# LiPo-PSU.net
KiCad netlist of a schematic drawn in EAGLE
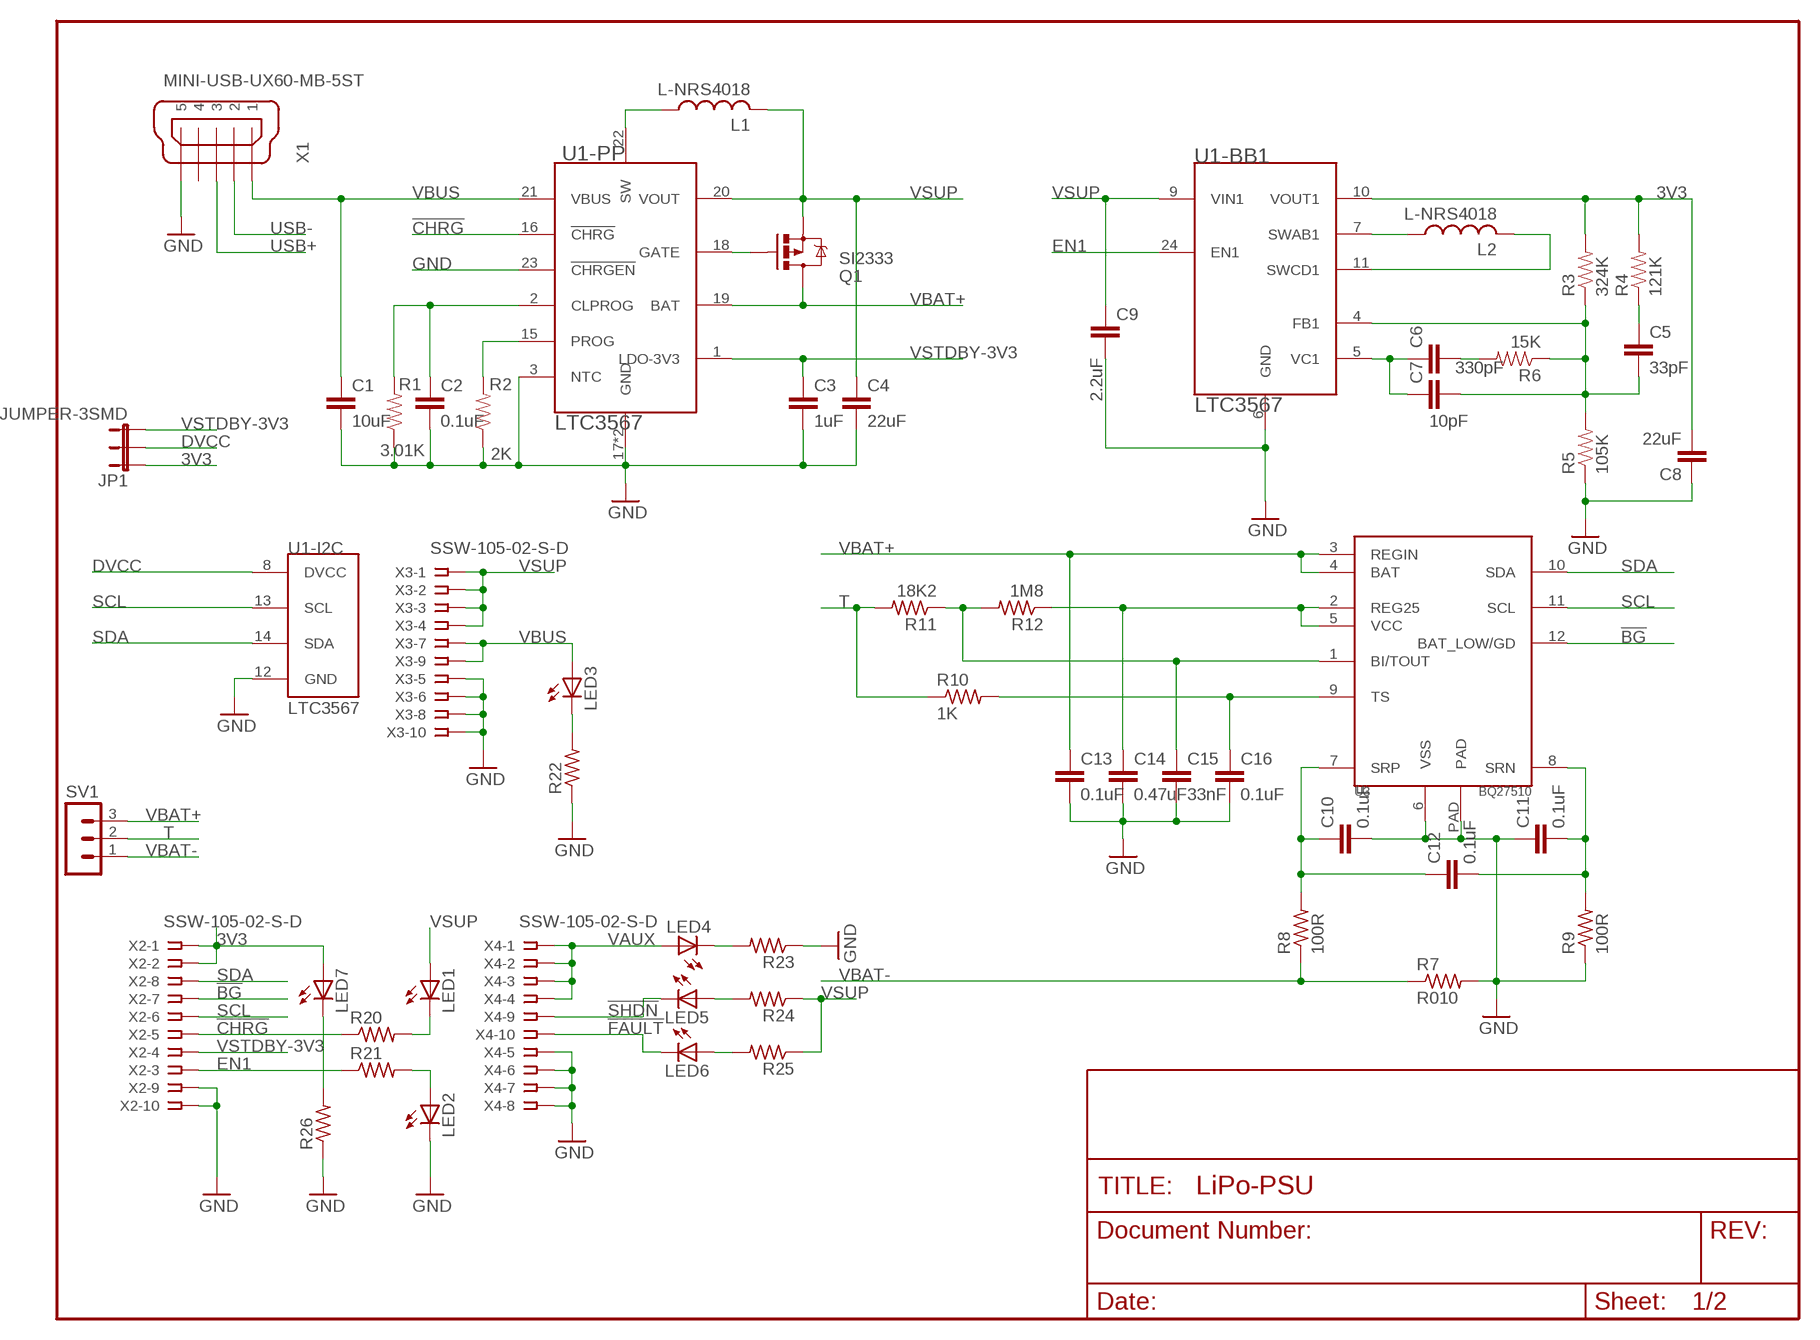
[diagram p0: schematic, sheet 1]
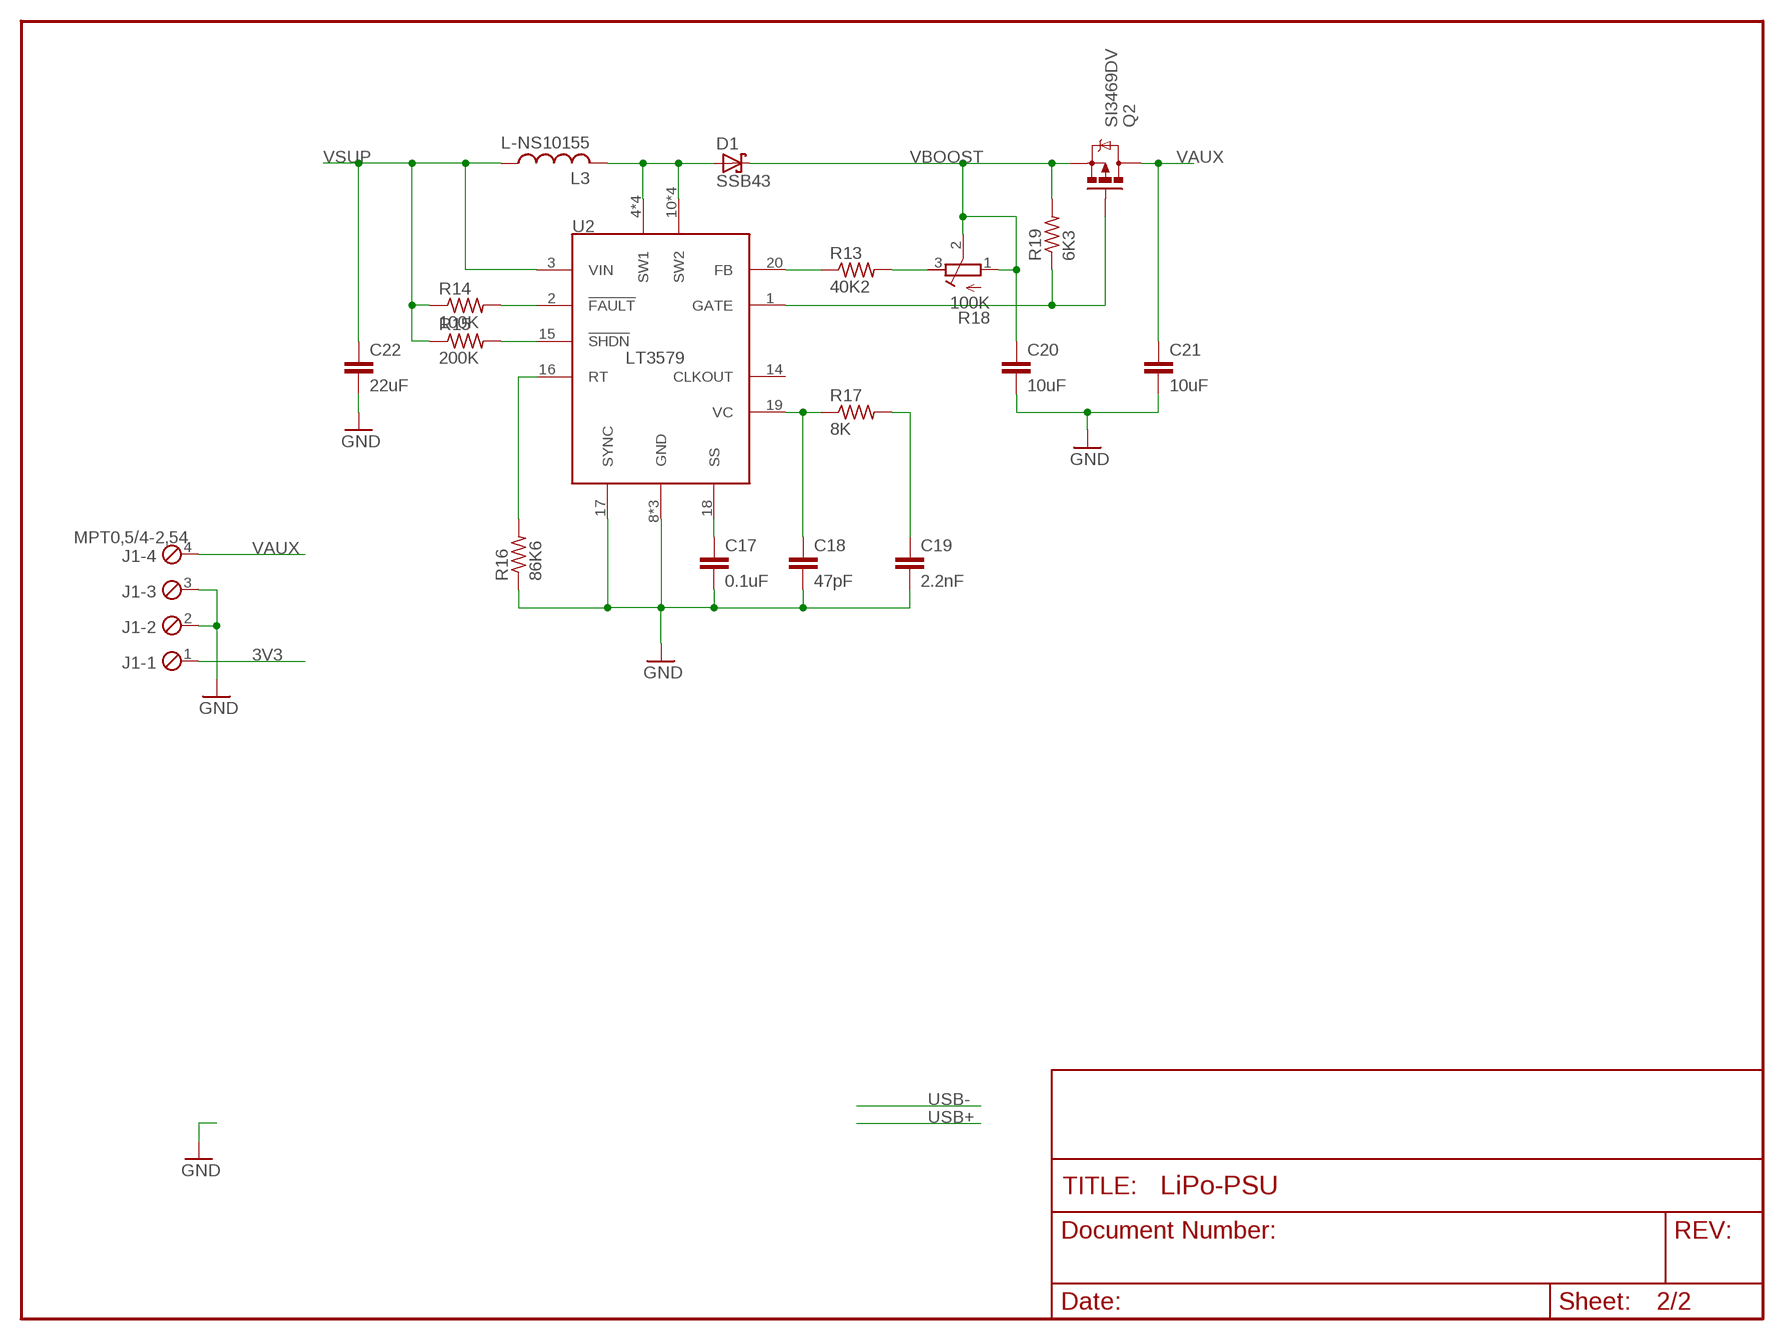
[diagram p1: schematic, sheet 2]

(export (version "E")
  (design (tool "Eeschema 10.0.6"))
  (components
    (comp (ref "C17")
      (value "0.1uF")
      (footprint "eagle-import:C0402")
      (libsource (lib "eagle-import") (part "C-EUC0402"))
    )
    (comp (ref "C18")
      (value "47pF")
      (footprint "eagle-import:C0402")
      (libsource (lib "eagle-import") (part "C-EUC0402"))
    )
    (comp (ref "C19")
      (value "2.2nF")
      (footprint "eagle-import:C0402")
      (libsource (lib "eagle-import") (part "C-EUC0402"))
    )
    (comp (ref "C20")
      (value "10uF")
      (footprint "eagle-import:C0805")
      (libsource (lib "eagle-import") (part "C-EUC0805"))
    )
    (comp (ref "C21")
      (value "10uF")
      (footprint "eagle-import:C0805")
      (libsource (lib "eagle-import") (part "C-EUC0805"))
    )
    (comp (ref "C22")
      (value "22uF")
      (footprint "eagle-import:C0805")
      (libsource (lib "eagle-import") (part "C-EUC0805"))
    )
    (comp (ref "D1")
      (value "SSB43")
      (footprint "eagle-import:SMB")
      (libsource (lib "eagle-import") (part "MBRS130LT3"))
    )
    (comp (ref "J1")
      (value "MPT0,5/4-2,54")
      (footprint "eagle-import:MPT0,5_4-2,54")
      (libsource (lib "eagle-import") (part "MPT0,5/4-2,54"))
    )
    (comp (ref "L3")
      (value "L-NS10155")
      (footprint "eagle-import:NS10155")
      (libsource (lib "eagle-import") (part "L-NS10155"))
    )
    (comp (ref "Q2")
      (value "SI3469DV")
      (footprint "eagle-import:TSOP-6")
      (libsource (lib "eagle-import") (part "MOSFET-PCHANNELTSOP6"))
    )
    (comp (ref "R13")
      (value "40K2")
      (footprint "eagle-import:R0402")
      (libsource (lib "eagle-import") (part "R-US_R0402"))
    )
    (comp (ref "R14")
      (value "100K")
      (footprint "eagle-import:R0402")
      (libsource (lib "eagle-import") (part "R-US_R0402"))
    )
    (comp (ref "R15")
      (value "200K")
      (footprint "eagle-import:R0402")
      (libsource (lib "eagle-import") (part "R-US_R0402"))
    )
    (comp (ref "R16")
      (value "86K6")
      (footprint "eagle-import:R0402")
      (libsource (lib "eagle-import") (part "R-US_R0402"))
    )
    (comp (ref "R17")
      (value "8K")
      (footprint "eagle-import:R0402")
      (libsource (lib "eagle-import") (part "R-US_R0402"))
    )
    (comp (ref "R18")
      (value "100K")
      (footprint "eagle-import:RTRIM3214W")
      (libsource (lib "eagle-import") (part "R-TRIMM3214W"))
    )
    (comp (ref "R19")
      (value "6K3")
      (footprint "eagle-import:R0402")
      (libsource (lib "eagle-import") (part "R-US_R0402"))
    )
    (comp (ref "U2")
      (value "LT3579")
      (footprint "eagle-import:QFN20-4X5(UFD)")
      (libsource (lib "eagle-import") (part "LT3579"))
    )
    (comp (ref "C1")
      (value "10uF")
      (footprint "eagle-import:0805")
      (libsource (lib "eagle-import") (part "CAP0805"))
    )
    (comp (ref "C2")
      (value "0.1uF")
      (footprint "eagle-import:0402-CAP")
      (libsource (lib "eagle-import") (part "CAP0402-CAP"))
    )
    (comp (ref "C3")
      (value "1uF")
      (footprint "eagle-import:0402-CAP")
      (libsource (lib "eagle-import") (part "CAP0402-CAP"))
    )
    (comp (ref "C4")
      (value "22uF")
      (footprint "eagle-import:0805")
      (libsource (lib "eagle-import") (part "CAP0805"))
    )
    (comp (ref "C5")
      (value "33pF")
      (footprint "eagle-import:0402-CAP")
      (libsource (lib "eagle-import") (part "CAP0402-CAP"))
    )
    (comp (ref "C6")
      (value "330pF")
      (footprint "eagle-import:0402-CAP")
      (libsource (lib "eagle-import") (part "CAP0402-CAP"))
    )
    (comp (ref "C7")
      (value "10pF")
      (footprint "eagle-import:0402-CAP")
      (libsource (lib "eagle-import") (part "CAP0402-CAP"))
    )
    (comp (ref "C8")
      (value "22uF")
      (footprint "eagle-import:0805")
      (libsource (lib "eagle-import") (part "CAP0805"))
    )
    (comp (ref "C9")
      (value "2.2uF")
      (footprint "eagle-import:0402-CAP")
      (libsource (lib "eagle-import") (part "CAP0402-CAP"))
    )
    (comp (ref "C10")
      (value "0.1uF")
      (footprint "eagle-import:C0402")
      (libsource (lib "eagle-import") (part "C-EUC0402"))
    )
    (comp (ref "C11")
      (value "0.1uF")
      (footprint "eagle-import:C0402")
      (libsource (lib "eagle-import") (part "C-EUC0402"))
    )
    (comp (ref "C12")
      (value "0.1uF")
      (footprint "eagle-import:C0402")
      (libsource (lib "eagle-import") (part "C-EUC0402"))
    )
    (comp (ref "C13")
      (value "0.1uF")
      (footprint "eagle-import:C0402")
      (libsource (lib "eagle-import") (part "C-EUC0402"))
    )
    (comp (ref "C14")
      (value "0.47uF")
      (footprint "eagle-import:C0402")
      (libsource (lib "eagle-import") (part "C-EUC0402"))
    )
    (comp (ref "C15")
      (value "33nF")
      (footprint "eagle-import:C0402")
      (libsource (lib "eagle-import") (part "C-EUC0402"))
    )
    (comp (ref "C16")
      (value "0.1uF")
      (footprint "eagle-import:C0402")
      (libsource (lib "eagle-import") (part "C-EUC0402"))
    )
    (comp (ref "JP1")
      (value "JUMPER-3SMD")
      (footprint "eagle-import:SJ_3")
      (libsource (lib "eagle-import") (part "JUMPER-3SMD"))
    )
    (comp (ref "L1")
      (value "L-NRS4018")
      (footprint "eagle-import:NR(S)401X")
      (libsource (lib "eagle-import") (part "L-NRS4018"))
    )
    (comp (ref "L2")
      (value "L-NRS4018")
      (footprint "eagle-import:NR(S)401X")
      (libsource (lib "eagle-import") (part "L-NRS4018"))
    )
    (comp (ref "LED1")
      (value "LEDCHIP-LED0603")
      (footprint "eagle-import:CHIP-LED0603")
      (libsource (lib "eagle-import") (part "LEDCHIP-LED0603"))
    )
    (comp (ref "LED2")
      (value "LEDCHIP-LED0603")
      (footprint "eagle-import:CHIP-LED0603")
      (libsource (lib "eagle-import") (part "LEDCHIP-LED0603"))
    )
    (comp (ref "LED3")
      (value "LEDCHIP-LED0603")
      (footprint "eagle-import:CHIP-LED0603")
      (libsource (lib "eagle-import") (part "LEDCHIP-LED0603"))
    )
    (comp (ref "LED4")
      (value "LEDCHIP-LED0603")
      (footprint "eagle-import:CHIP-LED0603")
      (libsource (lib "eagle-import") (part "LEDCHIP-LED0603"))
    )
    (comp (ref "LED5")
      (value "LEDCHIP-LED0603")
      (footprint "eagle-import:CHIP-LED0603")
      (libsource (lib "eagle-import") (part "LEDCHIP-LED0603"))
    )
    (comp (ref "LED6")
      (value "LEDCHIP-LED0603")
      (footprint "eagle-import:CHIP-LED0603")
      (libsource (lib "eagle-import") (part "LEDCHIP-LED0603"))
    )
    (comp (ref "LED7")
      (value "LEDCHIP-LED0603")
      (footprint "eagle-import:CHIP-LED0603")
      (libsource (lib "eagle-import") (part "LEDCHIP-LED0603"))
    )
    (comp (ref "Q1")
      (value "SI2333")
      (footprint "eagle-import:SOT23-3")
      (libsource (lib "eagle-import") (part "SI2333"))
    )
    (comp (ref "R1")
      (value "3.01K")
      (footprint "eagle-import:0402-RES")
      (libsource (lib "eagle-import") (part "RESISTOR0402-RES"))
    )
    (comp (ref "R2")
      (value "2K")
      (footprint "eagle-import:0402-RES")
      (libsource (lib "eagle-import") (part "RESISTOR0402-RES"))
    )
    (comp (ref "R3")
      (value "324K")
      (footprint "eagle-import:0402-RES")
      (libsource (lib "eagle-import") (part "RESISTOR0402-RES"))
    )
    (comp (ref "R4")
      (value "121K")
      (footprint "eagle-import:0402-RES")
      (libsource (lib "eagle-import") (part "RESISTOR0402-RES"))
    )
    (comp (ref "R5")
      (value "105K")
      (footprint "eagle-import:0402-RES")
      (libsource (lib "eagle-import") (part "RESISTOR0402-RES"))
    )
    (comp (ref "R6")
      (value "15K")
      (footprint "eagle-import:0402-RES")
      (libsource (lib "eagle-import") (part "RESISTOR0402-RES"))
    )
    (comp (ref "R7")
      (value "R010")
      (footprint "eagle-import:R2512")
      (libsource (lib "eagle-import") (part "R-US_R2512"))
    )
    (comp (ref "R8")
      (value "100R")
      (footprint "eagle-import:R0402")
      (libsource (lib "eagle-import") (part "R-US_R0402"))
    )
    (comp (ref "R9")
      (value "100R")
      (footprint "eagle-import:R0402")
      (libsource (lib "eagle-import") (part "R-US_R0402"))
    )
    (comp (ref "R10")
      (value "1K")
      (footprint "eagle-import:R0402")
      (libsource (lib "eagle-import") (part "R-US_R0402"))
    )
    (comp (ref "R11")
      (value "18K2")
      (footprint "eagle-import:R0402")
      (libsource (lib "eagle-import") (part "R-US_R0402"))
    )
    (comp (ref "R12")
      (value "1M8")
      (footprint "eagle-import:R0402")
      (libsource (lib "eagle-import") (part "R-US_R0402"))
    )
    (comp (ref "R20")
      (value "R-US_R0402")
      (footprint "eagle-import:R0402")
      (libsource (lib "eagle-import") (part "R-US_R0402"))
    )
    (comp (ref "R21")
      (value "R-US_R0402")
      (footprint "eagle-import:R0402")
      (libsource (lib "eagle-import") (part "R-US_R0402"))
    )
    (comp (ref "R22")
      (value "R-US_R0402")
      (footprint "eagle-import:R0402")
      (libsource (lib "eagle-import") (part "R-US_R0402"))
    )
    (comp (ref "R23")
      (value "R-US_R0402")
      (footprint "eagle-import:R0402")
      (libsource (lib "eagle-import") (part "R-US_R0402"))
    )
    (comp (ref "R24")
      (value "R-US_R0402")
      (footprint "eagle-import:R0402")
      (libsource (lib "eagle-import") (part "R-US_R0402"))
    )
    (comp (ref "R25")
      (value "R-US_R0402")
      (footprint "eagle-import:R0402")
      (libsource (lib "eagle-import") (part "R-US_R0402"))
    )
    (comp (ref "R26")
      (value "R-US_R0402")
      (footprint "eagle-import:R0402")
      (libsource (lib "eagle-import") (part "R-US_R0402"))
    )
    (comp (ref "SV1")
      (value "MA03-1")
      (footprint "eagle-import:MA03-1")
      (libsource (lib "eagle-import") (part "MA03-1"))
    )
    (comp (ref "U1")
      (value "LTC3567")
      (footprint "eagle-import:QFN24-4X4(UF)")
      (libsource (lib "eagle-import") (part "LTC3567"))
    )
    (comp (ref "U3")
      (value "BQ27510")
      (footprint "eagle-import:DRZ(S-PDSO-N12)")
      (libsource (lib "eagle-import") (part "BQ27510"))
    )
    (comp (ref "X1")
      (value "MINI-USB-UX60-MB-5ST")
      (footprint "eagle-import:UX60-MB-5ST")
      (libsource (lib "eagle-import") (part "MINI-USB-UX60-MB-5ST"))
    )
    (comp (ref "X2")
      (value "SSW-105-02-S-D")
      (footprint "eagle-import:SSW-105-02-S-D")
      (libsource (lib "eagle-import") (part "SSW-105-02-S-D"))
    )
    (comp (ref "X3")
      (value "SSW-105-02-S-D")
      (footprint "eagle-import:SSW-105-02-S-D")
      (libsource (lib "eagle-import") (part "SSW-105-02-S-D"))
    )
    (comp (ref "X4")
      (value "SSW-105-02-S-D")
      (footprint "eagle-import:SSW-105-02-S-D")
      (libsource (lib "eagle-import") (part "SSW-105-02-S-D"))
    )
  )
  (nets
    (net (code "1") (name "3V3") (class "Default")
      (node (ref "C8") (pin "2") (pinfunction "2_2") (pintype "passive"))
      (node (ref "J1") (pin "1") (pinfunction "1_1") (pintype "passive"))
      (node (ref "JP1") (pin "1") (pinfunction "1_1") (pintype "passive"))
      (node (ref "LED7") (pin "A") (pinfunction "A_A") (pintype "passive"))
      (node (ref "R3") (pin "2") (pinfunction "2_2") (pintype "passive"))
      (node (ref "R4") (pin "2") (pinfunction "2_2") (pintype "passive"))
      (node (ref "U1") (pin "10") (pinfunction "VOUT1_10") (pintype "output"))
      (node (ref "X2") (pin "1") (pinfunction "1_1") (pintype "passive"))
      (node (ref "X2") (pin "2") (pinfunction "1_2") (pintype "passive"))
    )
    (net (code "2") (name "DVCC") (class "Default")
      (node (ref "JP1") (pin "2") (pinfunction "2_2") (pintype "passive"))
      (node (ref "U1") (pin "8") (pinfunction "DVCC_8") (pintype "input"))
    )
    (net (code "3") (name "EN1") (class "Default")
      (node (ref "R21") (pin "1") (pinfunction "1_1") (pintype "passive"))
      (node (ref "U1") (pin "24") (pinfunction "EN1_24") (pintype "input"))
      (node (ref "X2") (pin "3") (pinfunction "1_3") (pintype "passive"))
    )
    (net (code "4") (name "GND") (class "Default")
      (node (ref "C1") (pin "2") (pinfunction "2_2") (pintype "passive"))
      (node (ref "C10") (pin "2") (pinfunction "2_2") (pintype "passive"))
      (node (ref "C11") (pin "1") (pinfunction "1_1") (pintype "passive"))
      (node (ref "C13") (pin "2") (pinfunction "2_2") (pintype "passive"))
      (node (ref "C14") (pin "2") (pinfunction "2_2") (pintype "passive"))
      (node (ref "C15") (pin "2") (pinfunction "2_2") (pintype "passive"))
      (node (ref "C16") (pin "2") (pinfunction "2_2") (pintype "passive"))
      (node (ref "C17") (pin "2") (pinfunction "2_2") (pintype "passive"))
      (node (ref "C18") (pin "2") (pinfunction "2_2") (pintype "passive"))
      (node (ref "C19") (pin "2") (pinfunction "2_2") (pintype "passive"))
      (node (ref "C2") (pin "2") (pinfunction "2_2") (pintype "passive"))
      (node (ref "C20") (pin "2") (pinfunction "2_2") (pintype "passive"))
      (node (ref "C21") (pin "2") (pinfunction "2_2") (pintype "passive"))
      (node (ref "C22") (pin "2") (pinfunction "2_2") (pintype "passive"))
      (node (ref "C3") (pin "2") (pinfunction "2_2") (pintype "passive"))
      (node (ref "C4") (pin "2") (pinfunction "2_2") (pintype "passive"))
      (node (ref "C8") (pin "1") (pinfunction "1_1") (pintype "passive"))
      (node (ref "C9") (pin "2") (pinfunction "2_2") (pintype "passive"))
      (node (ref "J1") (pin "2") (pinfunction "1_2") (pintype "passive"))
      (node (ref "J1") (pin "3") (pinfunction "1_3") (pintype "passive"))
      (node (ref "LED2") (pin "C") (pinfunction "C_C") (pintype "passive"))
      (node (ref "R1") (pin "1") (pinfunction "1_1") (pintype "passive"))
      (node (ref "R16") (pin "1") (pinfunction "1_1") (pintype "passive"))
      (node (ref "R2") (pin "1") (pinfunction "1_1") (pintype "passive"))
      (node (ref "R22") (pin "1") (pinfunction "1_1") (pintype "passive"))
      (node (ref "R23") (pin "1") (pinfunction "1_1") (pintype "passive"))
      (node (ref "R26") (pin "1") (pinfunction "1_1") (pintype "passive"))
      (node (ref "R5") (pin "1") (pinfunction "1_1") (pintype "passive"))
      (node (ref "R7") (pin "2") (pinfunction "2_2") (pintype "passive"))
      (node (ref "R9") (pin "1") (pinfunction "1_1") (pintype "passive"))
      (node (ref "U1") (pin "12") (pinfunction "GND_12") (pintype "power_in"))
      (node (ref "U1") (pin "17") (pinfunction "GND_17") (pintype "power_in"))
      (node (ref "U1") (pin "23") (pinfunction "~{CHRGEN}_23") (pintype "input"))
      (node (ref "U1") (pin "3") (pinfunction "NTC_3") (pintype "bidirectional"))
      (node (ref "U1") (pin "6") (pinfunction "GND_6") (pintype "power_in"))
      (node (ref "U1") (pin "PAD") (pinfunction "GND_PAD") (pintype "power_in"))
      (node (ref "U2") (pin "17") (pinfunction "SYNC_17") (pintype "input"))
      (node (ref "U2") (pin "8") (pinfunction "GND_8") (pintype "power_in"))
      (node (ref "U2") (pin "9") (pinfunction "GND_9") (pintype "power_in"))
      (node (ref "U2") (pin "PAD") (pinfunction "GND_PAD") (pintype "power_in"))
      (node (ref "U3") (pin "6") (pinfunction "VSS_6") (pintype "power_in"))
      (node (ref "U3") (pin "PAD") (pinfunction "PAD_PAD") (pintype "power_in"))
      (node (ref "X1") (pin "5") (pinfunction "5_5") (pintype "input"))
      (node (ref "X2") (pin "10") (pinfunction "1_10") (pintype "passive"))
      (node (ref "X2") (pin "9") (pinfunction "1_9") (pintype "passive"))
      (node (ref "X3") (pin "10") (pinfunction "1_10") (pintype "passive"))
      (node (ref "X3") (pin "5") (pinfunction "1_5") (pintype "passive"))
      (node (ref "X3") (pin "6") (pinfunction "1_6") (pintype "passive"))
      (node (ref "X3") (pin "8") (pinfunction "1_8") (pintype "passive"))
      (node (ref "X4") (pin "5") (pinfunction "1_5") (pintype "passive"))
      (node (ref "X4") (pin "6") (pinfunction "1_6") (pintype "passive"))
      (node (ref "X4") (pin "7") (pinfunction "1_7") (pintype "passive"))
      (node (ref "X4") (pin "8") (pinfunction "1_8") (pintype "passive"))
    )
    (net (code "5") (name "Net-(C5-Pad1)") (class "Default")
      (node (ref "C5") (pin "1") (pinfunction "1_1") (pintype "passive"))
      (node (ref "R4") (pin "1") (pinfunction "1_1") (pintype "passive"))
    )
    (net (code "6") (name "Net-(C6-Pad2)") (class "Default")
      (node (ref "C6") (pin "2") (pinfunction "2_2") (pintype "passive"))
      (node (ref "R6") (pin "2") (pinfunction "2_2") (pintype "passive"))
    )
    (net (code "7") (name "Net-(C19-Pad1)") (class "Default")
      (node (ref "C19") (pin "1") (pinfunction "1_1") (pintype "passive"))
      (node (ref "R17") (pin "2") (pinfunction "2_2") (pintype "passive"))
    )
    (net (code "8") (name "Net-(D1-PadA)") (class "Default")
      (node (ref "D1") (pin "A") (pinfunction "A_A") (pintype "passive"))
      (node (ref "L3") (pin "2") (pinfunction "2_2") (pintype "passive"))
      (node (ref "U2") (pin "10") (pinfunction "SW2_10") (pintype "bidirectional"))
      (node (ref "U2") (pin "11") (pinfunction "SW2_11") (pintype "bidirectional"))
      (node (ref "U2") (pin "12") (pinfunction "SW2_12") (pintype "bidirectional"))
      (node (ref "U2") (pin "13") (pinfunction "SW2_13") (pintype "bidirectional"))
      (node (ref "U2") (pin "4") (pinfunction "SW1_4") (pintype "bidirectional"))
      (node (ref "U2") (pin "5") (pinfunction "SW1_5") (pintype "bidirectional"))
      (node (ref "U2") (pin "6") (pinfunction "SW1_6") (pintype "bidirectional"))
      (node (ref "U2") (pin "7") (pinfunction "SW1_7") (pintype "bidirectional"))
    )
    (net (code "9") (name "Net-(LED1-PadC)") (class "Default")
      (node (ref "LED1") (pin "C") (pinfunction "C_C") (pintype "passive"))
      (node (ref "R20") (pin "2") (pinfunction "2_2") (pintype "passive"))
    )
    (net (code "10") (name "Net-(LED2-PadA)") (class "Default")
      (node (ref "LED2") (pin "A") (pinfunction "A_A") (pintype "passive"))
      (node (ref "R21") (pin "2") (pinfunction "2_2") (pintype "passive"))
    )
    (net (code "11") (name "Net-(LED3-PadC)") (class "Default")
      (node (ref "LED3") (pin "C") (pinfunction "C_C") (pintype "passive"))
      (node (ref "R22") (pin "2") (pinfunction "2_2") (pintype "passive"))
    )
    (net (code "12") (name "Net-(LED4-PadC)") (class "Default")
      (node (ref "LED4") (pin "C") (pinfunction "C_C") (pintype "passive"))
      (node (ref "R23") (pin "2") (pinfunction "2_2") (pintype "passive"))
    )
    (net (code "13") (name "Net-(LED5-PadA)") (class "Default")
      (node (ref "LED5") (pin "A") (pinfunction "A_A") (pintype "passive"))
      (node (ref "R24") (pin "2") (pinfunction "2_2") (pintype "passive"))
    )
    (net (code "14") (name "Net-(LED6-PadA)") (class "Default")
      (node (ref "LED6") (pin "A") (pinfunction "A_A") (pintype "passive"))
      (node (ref "R25") (pin "2") (pinfunction "2_2") (pintype "passive"))
    )
    (net (code "15") (name "Net-(LED7-PadC)") (class "Default")
      (node (ref "LED7") (pin "C") (pinfunction "C_C") (pintype "passive"))
      (node (ref "R26") (pin "2") (pinfunction "2_2") (pintype "passive"))
    )
    (net (code "16") (name "Net-(Q1-G)") (class "Default")
      (node (ref "Q1") (pin "1") (pinfunction "G_1") (pintype "passive"))
      (node (ref "U1") (pin "18") (pinfunction "GATE_18") (pintype "bidirectional"))
    )
    (net (code "17") (name "Net-(Q2-G)") (class "Default")
      (node (ref "Q2") (pin "3") (pinfunction "G_3") (pintype "passive"))
      (node (ref "R19") (pin "1") (pinfunction "1_1") (pintype "passive"))
      (node (ref "U2") (pin "1") (pinfunction "GATE_1") (pintype "bidirectional"))
    )
    (net (code "18") (name "Net-(R18-A)") (class "Default")
      (node (ref "R13") (pin "2") (pinfunction "2_2") (pintype "passive"))
      (node (ref "R18") (pin "3") (pinfunction "A_3") (pintype "passive"))
    )
    (net (code "19") (name "Net-(U1A-FB1)") (class "Default")
      (node (ref "C5") (pin "2") (pinfunction "2_2") (pintype "passive"))
      (node (ref "C7") (pin "2") (pinfunction "2_2") (pintype "passive"))
      (node (ref "R3") (pin "1") (pinfunction "1_1") (pintype "passive"))
      (node (ref "R5") (pin "2") (pinfunction "2_2") (pintype "passive"))
      (node (ref "R6") (pin "1") (pinfunction "1_1") (pintype "passive"))
      (node (ref "U1") (pin "4") (pinfunction "FB1_4") (pintype "bidirectional"))
    )
    (net (code "20") (name "Net-(U1A-SWAB1)") (class "Default")
      (node (ref "L2") (pin "1") (pinfunction "1_1") (pintype "passive"))
      (node (ref "U1") (pin "7") (pinfunction "SWAB1_7") (pintype "bidirectional"))
    )
    (net (code "21") (name "Net-(U1A-SWCD1)") (class "Default")
      (node (ref "L2") (pin "2") (pinfunction "2_2") (pintype "passive"))
      (node (ref "U1") (pin "11") (pinfunction "SWCD1_11") (pintype "bidirectional"))
    )
    (net (code "22") (name "Net-(U1A-VC1)") (class "Default")
      (node (ref "C6") (pin "1") (pinfunction "1_1") (pintype "passive"))
      (node (ref "C7") (pin "1") (pinfunction "1_1") (pintype "passive"))
      (node (ref "U1") (pin "5") (pinfunction "VC1_5") (pintype "bidirectional"))
    )
    (net (code "23") (name "Net-(U1C-CLPROG)") (class "Default")
      (node (ref "C2") (pin "1") (pinfunction "1_1") (pintype "passive"))
      (node (ref "R1") (pin "2") (pinfunction "2_2") (pintype "passive"))
      (node (ref "U1") (pin "2") (pinfunction "CLPROG_2") (pintype "bidirectional"))
    )
    (net (code "24") (name "Net-(U1C-PROG)") (class "Default")
      (node (ref "R2") (pin "2") (pinfunction "2_2") (pintype "passive"))
      (node (ref "U1") (pin "15") (pinfunction "PROG_15") (pintype "bidirectional"))
    )
    (net (code "25") (name "Net-(U1C-SW)") (class "Default")
      (node (ref "L1") (pin "1") (pinfunction "1_1") (pintype "passive"))
      (node (ref "U1") (pin "22") (pinfunction "SW_22") (pintype "bidirectional"))
    )
    (net (code "26") (name "Net-(U2-FB)") (class "Default")
      (node (ref "R13") (pin "1") (pinfunction "1_1") (pintype "passive"))
      (node (ref "U2") (pin "20") (pinfunction "FB_20") (pintype "bidirectional"))
    )
    (net (code "27") (name "Net-(U2-RT)") (class "Default")
      (node (ref "R16") (pin "2") (pinfunction "2_2") (pintype "passive"))
      (node (ref "U2") (pin "16") (pinfunction "RT_16") (pintype "input"))
    )
    (net (code "28") (name "Net-(U2-SS)") (class "Default")
      (node (ref "C17") (pin "1") (pinfunction "1_1") (pintype "passive"))
      (node (ref "U2") (pin "18") (pinfunction "SS_18") (pintype "input"))
    )
    (net (code "29") (name "Net-(U2-VC)") (class "Default")
      (node (ref "C18") (pin "1") (pinfunction "1_1") (pintype "passive"))
      (node (ref "R17") (pin "1") (pinfunction "1_1") (pintype "passive"))
      (node (ref "U2") (pin "19") (pinfunction "VC_19") (pintype "bidirectional"))
    )
    (net (code "30") (name "Net-(U3-BI{slash}TOUT)") (class "Default")
      (node (ref "C15") (pin "1") (pinfunction "1_1") (pintype "passive"))
      (node (ref "R11") (pin "1") (pinfunction "1_1") (pintype "passive"))
      (node (ref "R12") (pin "2") (pinfunction "2_2") (pintype "passive"))
      (node (ref "U3") (pin "1") (pinfunction "BI/TOUT_1") (pintype "bidirectional"))
    )
    (net (code "31") (name "Net-(U3-REG25)") (class "Default")
      (node (ref "C14") (pin "1") (pinfunction "1_1") (pintype "passive"))
      (node (ref "R12") (pin "1") (pinfunction "1_1") (pintype "passive"))
      (node (ref "U3") (pin "2") (pinfunction "REG25_2") (pintype "power_in"))
      (node (ref "U3") (pin "5") (pinfunction "VCC_5") (pintype "power_in"))
    )
    (net (code "32") (name "Net-(U3-SRN)") (class "Default")
      (node (ref "C11") (pin "2") (pinfunction "2_2") (pintype "passive"))
      (node (ref "C12") (pin "2") (pinfunction "2_2") (pintype "passive"))
      (node (ref "R9") (pin "2") (pinfunction "2_2") (pintype "passive"))
      (node (ref "U3") (pin "8") (pinfunction "SRN_8") (pintype "input"))
    )
    (net (code "33") (name "Net-(U3-SRP)") (class "Default")
      (node (ref "C10") (pin "1") (pinfunction "1_1") (pintype "passive"))
      (node (ref "C12") (pin "1") (pinfunction "1_1") (pintype "passive"))
      (node (ref "R8") (pin "2") (pinfunction "2_2") (pintype "passive"))
      (node (ref "U3") (pin "7") (pinfunction "SRP_7") (pintype "input"))
    )
    (net (code "34") (name "Net-(U3-TS)") (class "Default")
      (node (ref "C16") (pin "1") (pinfunction "1_1") (pintype "passive"))
      (node (ref "R10") (pin "2") (pinfunction "2_2") (pintype "passive"))
      (node (ref "U3") (pin "9") (pinfunction "TS_9") (pintype "input"))
    )
    (net (code "35") (name "SCL") (class "Default")
      (node (ref "U1") (pin "13") (pinfunction "SCL_13") (pintype "input"))
      (node (ref "U3") (pin "11") (pinfunction "SCL_11") (pintype "input"))
      (node (ref "X2") (pin "6") (pinfunction "1_6") (pintype "passive"))
    )
    (net (code "36") (name "SDA") (class "Default")
      (node (ref "U1") (pin "14") (pinfunction "SDA_14") (pintype "input"))
      (node (ref "U3") (pin "10") (pinfunction "SDA_10") (pintype "open_collector"))
      (node (ref "X2") (pin "8") (pinfunction "1_8") (pintype "passive"))
    )
    (net (code "37") (name "T") (class "Default")
      (node (ref "R10") (pin "1") (pinfunction "1_1") (pintype "passive"))
      (node (ref "R11") (pin "2") (pinfunction "2_2") (pintype "passive"))
      (node (ref "SV1") (pin "2") (pinfunction "2_2") (pintype "passive"))
    )
    (net (code "38") (name "USB+") (class "Default")
      (node (ref "X1") (pin "3") (pinfunction "3_3") (pintype "input"))
    )
    (net (code "39") (name "USB-") (class "Default")
      (node (ref "X1") (pin "2") (pinfunction "2_2") (pintype "input"))
    )
    (net (code "40") (name "VAUX") (class "Default")
      (node (ref "C21") (pin "1") (pinfunction "1_1") (pintype "passive"))
      (node (ref "J1") (pin "4") (pinfunction "1_4") (pintype "passive"))
      (node (ref "LED4") (pin "A") (pinfunction "A_A") (pintype "passive"))
      (node (ref "Q2") (pin "1") (pinfunction "D_1") (pintype "passive"))
      (node (ref "Q2") (pin "2") (pinfunction "D_2") (pintype "passive"))
      (node (ref "Q2") (pin "5") (pinfunction "D_5") (pintype "passive"))
      (node (ref "Q2") (pin "6") (pinfunction "D_6") (pintype "passive"))
      (node (ref "X4") (pin "1") (pinfunction "1_1") (pintype "passive"))
      (node (ref "X4") (pin "2") (pinfunction "1_2") (pintype "passive"))
      (node (ref "X4") (pin "3") (pinfunction "1_3") (pintype "passive"))
      (node (ref "X4") (pin "4") (pinfunction "1_4") (pintype "passive"))
    )
    (net (code "41") (name "VBAT+") (class "Default")
      (node (ref "C13") (pin "1") (pinfunction "1_1") (pintype "passive"))
      (node (ref "Q1") (pin "3") (pinfunction "D_3") (pintype "passive"))
      (node (ref "SV1") (pin "3") (pinfunction "3_3") (pintype "passive"))
      (node (ref "U1") (pin "19") (pinfunction "BAT_19") (pintype "bidirectional"))
      (node (ref "U3") (pin "3") (pinfunction "REGIN_3") (pintype "power_in"))
      (node (ref "U3") (pin "4") (pinfunction "BAT_4") (pintype "input"))
    )
    (net (code "42") (name "VBAT-") (class "Default")
      (node (ref "R7") (pin "1") (pinfunction "1_1") (pintype "passive"))
      (node (ref "R8") (pin "1") (pinfunction "1_1") (pintype "passive"))
      (node (ref "SV1") (pin "1") (pinfunction "1_1") (pintype "passive"))
    )
    (net (code "43") (name "VBOOST") (class "Default")
      (node (ref "C20") (pin "1") (pinfunction "1_1") (pintype "passive"))
      (node (ref "D1") (pin "C") (pinfunction "C_C") (pintype "passive"))
      (node (ref "Q2") (pin "4") (pinfunction "S_4") (pintype "passive"))
      (node (ref "R18") (pin "1") (pinfunction "E_1") (pintype "passive"))
      (node (ref "R18") (pin "2") (pinfunction "S_2") (pintype "passive"))
      (node (ref "R19") (pin "2") (pinfunction "2_2") (pintype "passive"))
    )
    (net (code "44") (name "VBUS") (class "Default")
      (node (ref "C1") (pin "1") (pinfunction "1_1") (pintype "passive"))
      (node (ref "LED3") (pin "A") (pinfunction "A_A") (pintype "passive"))
      (node (ref "U1") (pin "21") (pinfunction "VBUS_21") (pintype "input"))
      (node (ref "X1") (pin "1") (pinfunction "1_1") (pintype "input"))
      (node (ref "X3") (pin "7") (pinfunction "1_7") (pintype "passive"))
      (node (ref "X3") (pin "9") (pinfunction "1_9") (pintype "passive"))
    )
    (net (code "45") (name "VSTDBY-3V3") (class "Default")
      (node (ref "C3") (pin "1") (pinfunction "1_1") (pintype "passive"))
      (node (ref "JP1") (pin "3") (pinfunction "3_3") (pintype "passive"))
      (node (ref "U1") (pin "1") (pinfunction "LDO-3V3_1") (pintype "bidirectional"))
      (node (ref "X2") (pin "4") (pinfunction "1_4") (pintype "passive"))
    )
    (net (code "46") (name "VSUP") (class "Default")
      (node (ref "C22") (pin "1") (pinfunction "1_1") (pintype "passive"))
      (node (ref "C4") (pin "1") (pinfunction "1_1") (pintype "passive"))
      (node (ref "C9") (pin "1") (pinfunction "1_1") (pintype "passive"))
      (node (ref "L1") (pin "2") (pinfunction "2_2") (pintype "passive"))
      (node (ref "L3") (pin "1") (pinfunction "1_1") (pintype "passive"))
      (node (ref "LED1") (pin "A") (pinfunction "A_A") (pintype "passive"))
      (node (ref "Q1") (pin "2") (pinfunction "S_2") (pintype "passive"))
      (node (ref "R14") (pin "1") (pinfunction "1_1") (pintype "passive"))
      (node (ref "R15") (pin "1") (pinfunction "1_1") (pintype "passive"))
      (node (ref "R24") (pin "1") (pinfunction "1_1") (pintype "passive"))
      (node (ref "R25") (pin "1") (pinfunction "1_1") (pintype "passive"))
      (node (ref "U1") (pin "20") (pinfunction "VOUT_20") (pintype "bidirectional"))
      (node (ref "U1") (pin "9") (pinfunction "VIN1_9") (pintype "input"))
      (node (ref "U2") (pin "3") (pinfunction "VIN_3") (pintype "input"))
      (node (ref "X3") (pin "1") (pinfunction "1_1") (pintype "passive"))
      (node (ref "X3") (pin "2") (pinfunction "1_2") (pintype "passive"))
      (node (ref "X3") (pin "3") (pinfunction "1_3") (pintype "passive"))
      (node (ref "X3") (pin "4") (pinfunction "1_4") (pintype "passive"))
    )
    (net (code "47") (name "unconnected-(U2-CLKOUT-Pad14)") (class "Default")
      (node (ref "U2") (pin "14") (pinfunction "CLKOUT_14") (pintype "bidirectional"))
    )
    (net (code "48") (name "unconnected-(X1-Pad4)") (class "Default")
      (node (ref "X1") (pin "4") (pinfunction "4_4") (pintype "input"))
    )
    (net (code "49") (name "~{BG}") (class "Default")
      (node (ref "U3") (pin "12") (pinfunction "BAT_LOW/GD_12") (pintype "open_collector"))
      (node (ref "X2") (pin "7") (pinfunction "1_7") (pintype "passive"))
    )
    (net (code "50") (name "~{CHRG}") (class "Default")
      (node (ref "R20") (pin "1") (pinfunction "1_1") (pintype "passive"))
      (node (ref "U1") (pin "16") (pinfunction "~{CHRG}_16") (pintype "open_collector"))
      (node (ref "X2") (pin "5") (pinfunction "1_5") (pintype "passive"))
    )
    (net (code "51") (name "~{FAULT}") (class "Default")
      (node (ref "LED6") (pin "C") (pinfunction "C_C") (pintype "passive"))
      (node (ref "R14") (pin "2") (pinfunction "2_2") (pintype "passive"))
      (node (ref "U2") (pin "2") (pinfunction "~{FAULT}_2") (pintype "open_collector"))
      (node (ref "X4") (pin "10") (pinfunction "1_10") (pintype "passive"))
    )
    (net (code "52") (name "~{SHDN}") (class "Default")
      (node (ref "LED5") (pin "C") (pinfunction "C_C") (pintype "passive"))
      (node (ref "R15") (pin "2") (pinfunction "2_2") (pintype "passive"))
      (node (ref "U2") (pin "15") (pinfunction "~{SHDN}_15") (pintype "input"))
      (node (ref "X4") (pin "9") (pinfunction "1_9") (pintype "passive"))
    )
  )
)
